# Power.net
KiCad netlist of a schematic drawn in Altium Designer
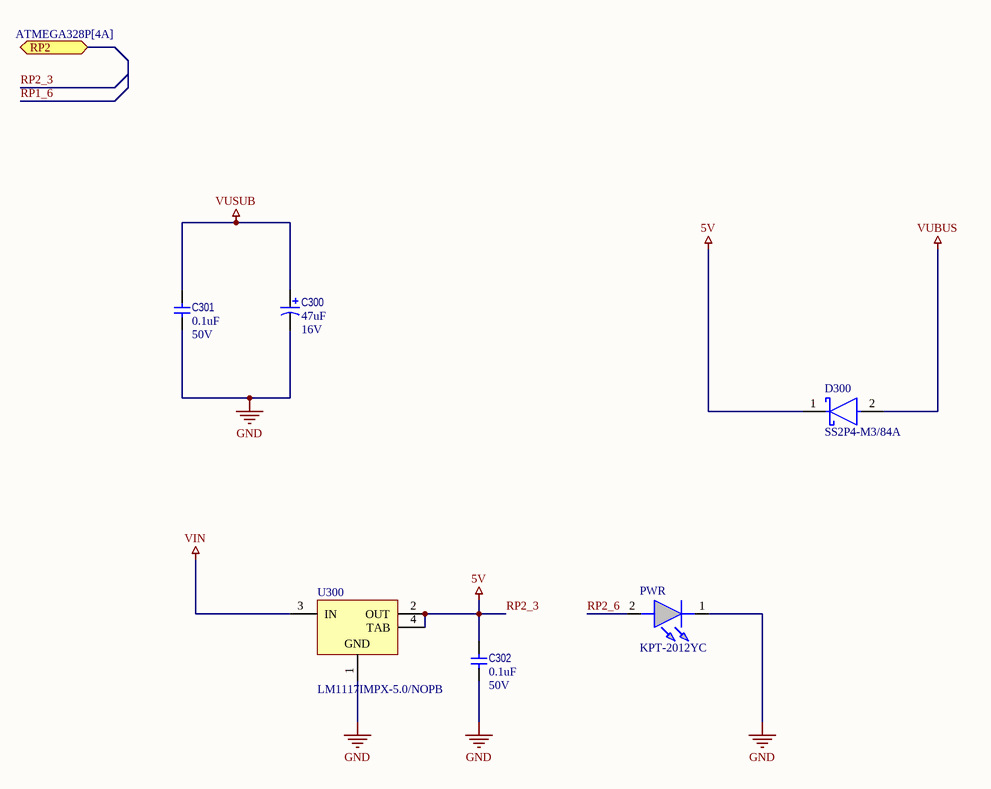
[diagram p0: Power.SchDoc]

(export (version "E")
  (design (tool "Eeschema 10.0.6"))
  (components
    (comp (ref "C300")
      (value "47uF")
      (footprint "CAPMP7343X430N")
      (description "CAP TANT 47uF ±20% 16V 2917 (7343 Metric)")
      (fields
        (field (name "VOLTAGE_RATING") "16V")
        (field (name "MANUFACTURER PART NUMBER") "16TQC47MW")
        (field (name "MANUFACTURER") "Panasonic")
        (field (name "CREATED BY") "rclemmons")
        (field (name "UPDATED BY") "rclemmons")
      )
      (libsource (lib "Parts") (part "CAP_POL"))
    )
    (comp (ref "C301")
      (value "0.1uF")
      (footprint "CAPC1005X55N")
      (description "CAP CER 0.1uF ±10% 50V X7R 0603 (1608 Metric)")
      (fields
        (field (name "VOLTAGE_RATING") "50V")
        (field (name "MANUFACTURER PART NUMBER") "C0603C104K5RECAUTO")
        (field (name "MANUFACTURER") "KEMET")
        (field (name "CREATED BY") "randy")
        (field (name "UPDATED BY") "randy")
      )
      (libsource (lib "Parts") (part "CAP_NOPOL"))
    )
    (comp (ref "C302")
      (value "0.1uF")
      (footprint "CAPC1005X55N")
      (description "CAP CER 0.1uF ±10% 50V X7R 0603 (1608 Metric)")
      (fields
        (field (name "VOLTAGE_RATING") "50V")
        (field (name "MANUFACTURER PART NUMBER") "C0603C104K5RECAUTO")
        (field (name "MANUFACTURER") "KEMET")
        (field (name "CREATED BY") "randy")
        (field (name "UPDATED BY") "randy")
      )
      (libsource (lib "Parts") (part "CAP_NOPOL"))
    )
    (comp (ref "D300")
      (value "SS2P4-M3/84A")
      (footprint "FP-96547-MFG")
      (description "DIODE SCHOTTKY 40V 2A DO220AA")
      (libsource (lib "Altium Content Vault") (part "1d6ec82d83fb6aee721767c19dac4b9"))
    )
    (comp (ref "PWR")
      (value "KPT-2012YC")
      (footprint "LEDC2012X75N")
      (description "Kingbright KPT-2012YC Yellow LED, 588 nm, 2012 (0805), Rectangle Lens SMD Package")
      (libsource (lib "KPT-2012YC") (part "KPT-2012YC"))
    )
    (comp (ref "U300")
      (value "LM1117IMPX-5.0/NOPB")
      (footprint "MP04A_M")
      (description "800mA Low-Dropout Linear Regulator, 4-pin SOT-223, Pb-Free")
      (fields (field (name "MANUFACTURER") "National Semiconductor"))
      (libsource (lib "Altium Content Vault") (part "PM-REG-LM1086-SOT4"))
    )
  )
  (nets
    (net (code "3") (name "/RP2_6") (class "Default")
      (node (ref "PWR") (pin "2") (pinfunction "A_2") (pintype "passive"))
    )
    (net (code "4") (name "5V") (class "Default")
      (node (ref "C302") (pin "1") (pinfunction "1_1") (pintype "passive"))
      (node (ref "D300") (pin "1") (pinfunction "C_1") (pintype "passive"))
      (node (ref "U300") (pin "2") (pinfunction "OUT_2") (pintype "power_in"))
      (node (ref "U300") (pin "4") (pinfunction "TAB_4") (pintype "power_in"))
    )
    (net (code "5") (name "GND") (class "Default")
      (node (ref "C300") (pin "2") (pinfunction "2_2") (pintype "passive"))
      (node (ref "C301") (pin "2") (pinfunction "2_2") (pintype "passive"))
      (node (ref "C302") (pin "2") (pinfunction "2_2") (pintype "passive"))
      (node (ref "PWR") (pin "1") (pinfunction "K_1") (pintype "passive"))
      (node (ref "U300") (pin "1") (pinfunction "GND_1") (pintype "power_in"))
    )
    (net (code "6") (name "VIN") (class "Default")
      (node (ref "U300") (pin "3") (pinfunction "IN_3") (pintype "power_in"))
    )
    (net (code "7") (name "VUBUS") (class "Default")
      (node (ref "D300") (pin "2") (pinfunction "A_2") (pintype "passive"))
    )
    (net (code "8") (name "VUSUB") (class "Default")
      (node (ref "C300") (pin "1") (pinfunction "1_1") (pintype "passive"))
      (node (ref "C301") (pin "1") (pinfunction "1_1") (pintype "passive"))
    )
  )
)
